# emonPi2C_V1_2.net
KiCad netlist of a schematic drawn in EAGLE
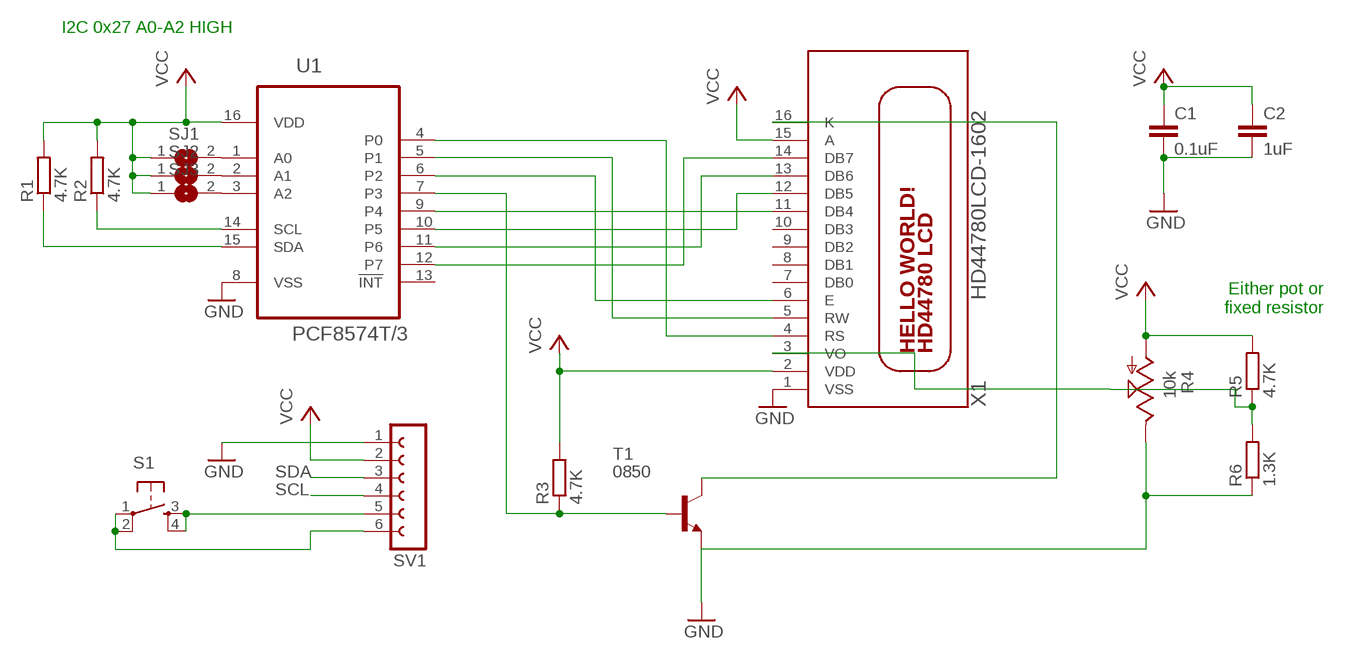
[diagram p0: schematic, sheet 1]

(export (version "E")
  (design (tool "Eeschema 10.0.6"))
  (components
    (comp (ref "C1")
      (value "0.1uF")
      (footprint "eagle-import:C0603")
      (libsource (lib "eagle-import") (part "C-EUC0603"))
    )
    (comp (ref "C2")
      (value "1uF")
      (footprint "eagle-import:C0603")
      (libsource (lib "eagle-import") (part "C-EUC0603"))
    )
    (comp (ref "R1")
      (value "4.7K")
      (footprint "eagle-import:R0603")
      (libsource (lib "eagle-import") (part "R-EU_R0603"))
    )
    (comp (ref "R2")
      (value "4.7K")
      (footprint "eagle-import:R0603")
      (libsource (lib "eagle-import") (part "R-EU_R0603"))
    )
    (comp (ref "R3")
      (value "4.7K")
      (footprint "eagle-import:R0603")
      (libsource (lib "eagle-import") (part "R-EU_R0603"))
    )
    (comp (ref "R4")
      (value "10k")
      (footprint "eagle-import:B25P")
      (libsource (lib "eagle-import") (part "TRIM_US-B25P"))
    )
    (comp (ref "R5")
      (value "4.7K")
      (footprint "eagle-import:R0603")
      (libsource (lib "eagle-import") (part "R-EU_R0603"))
    )
    (comp (ref "R6")
      (value "1.3K")
      (footprint "eagle-import:R0603")
      (libsource (lib "eagle-import") (part "R-EU_R0603"))
    )
    (comp (ref "S1")
      (value "TAC_SWITCHPTH")
      (footprint "eagle-import:TACTILE-PTH")
      (libsource (lib "eagle-import") (part "TAC_SWITCHPTH"))
    )
    (comp (ref "SJ1")
      (value "SOLDERJUMPERCLOSED")
      (footprint "eagle-import:SOLDERJUMPER_CLOSEDWIRE")
      (libsource (lib "eagle-import") (part "SOLDERJUMPERCLOSED"))
    )
    (comp (ref "SJ2")
      (value "SOLDERJUMPERCLOSED")
      (footprint "eagle-import:SOLDERJUMPER_CLOSEDWIRE")
      (libsource (lib "eagle-import") (part "SOLDERJUMPERCLOSED"))
    )
    (comp (ref "SJ3")
      (value "SOLDERJUMPERCLOSED")
      (footprint "eagle-import:SOLDERJUMPER_CLOSEDWIRE")
      (libsource (lib "eagle-import") (part "SOLDERJUMPERCLOSED"))
    )
    (comp (ref "SV1")
      (value "FE06-1")
      (footprint "eagle-import:FE06")
      (libsource (lib "eagle-import") (part "FE06-1"))
    )
    (comp (ref "T1")
      (value "0850")
      (footprint "eagle-import:SOT23")
      (libsource (lib "eagle-import") (part "BCX70SMD"))
    )
    (comp (ref "U1")
      (value "PCF8574T/3")
      (footprint "eagle-import:SOIC127P1032X265-16N")
      (libsource (lib "eagle-import") (part "PCF8574T/3"))
    )
    (comp (ref "X1")
      (value "HD44780LCD-1602")
      (footprint "eagle-import:LCD1602")
      (libsource (lib "eagle-import") (part "HD44780LCD-1602"))
    )
  )
  (nets
    (net (code "1") (name "/SCL") (class "Default")
      (node (ref "R2") (pin "1") (pinfunction "1_1") (pintype "passive"))
      (node (ref "SV1") (pin "4") (pinfunction "4_4") (pintype "passive"))
      (node (ref "U1") (pin "14") (pinfunction "SCL_14") (pintype "passive"))
    )
    (net (code "2") (name "/SDA") (class "Default")
      (node (ref "R1") (pin "1") (pinfunction "1_1") (pintype "passive"))
      (node (ref "SV1") (pin "3") (pinfunction "3_3") (pintype "passive"))
      (node (ref "U1") (pin "15") (pinfunction "SDA_15") (pintype "passive"))
    )
    (net (code "3") (name "GND") (class "Default")
      (node (ref "C1") (pin "2") (pinfunction "2_2") (pintype "passive"))
      (node (ref "C2") (pin "2") (pinfunction "2_2") (pintype "passive"))
      (node (ref "R4") (pin "E") (pinfunction "E_E") (pintype "passive"))
      (node (ref "R6") (pin "1") (pinfunction "1_1") (pintype "passive"))
      (node (ref "SV1") (pin "1") (pinfunction "1_1") (pintype "passive"))
      (node (ref "T1") (pin "2") (pinfunction "E_2") (pintype "passive"))
      (node (ref "U1") (pin "8") (pinfunction "VSS_8") (pintype "power_in"))
      (node (ref "X1") (pin "1") (pinfunction "VSS_1") (pintype "power_in"))
    )
    (net (code "4") (name "Net-(S1-Pad1)") (class "Default")
      (node (ref "S1") (pin "1") (pinfunction "1_1") (pintype "passive"))
      (node (ref "S1") (pin "2") (pinfunction "2_2") (pintype "passive"))
      (node (ref "SV1") (pin "6") (pinfunction "6_6") (pintype "passive"))
    )
    (net (code "5") (name "Net-(S1-Pad3)") (class "Default")
      (node (ref "S1") (pin "3") (pinfunction "3_3") (pintype "passive"))
      (node (ref "S1") (pin "4") (pinfunction "4_4") (pintype "passive"))
      (node (ref "SV1") (pin "5") (pinfunction "5_5") (pintype "passive"))
    )
    (net (code "6") (name "Net-(T1-B)") (class "Default")
      (node (ref "R3") (pin "1") (pinfunction "1_1") (pintype "passive"))
      (node (ref "T1") (pin "1") (pinfunction "B_1") (pintype "passive"))
      (node (ref "U1") (pin "7") (pinfunction "P3_7") (pintype "bidirectional"))
    )
    (net (code "7") (name "Net-(T1-C)") (class "Default")
      (node (ref "T1") (pin "3") (pinfunction "C_3") (pintype "passive"))
      (node (ref "X1") (pin "16") (pinfunction "K_16") (pintype "input"))
    )
    (net (code "8") (name "Net-(U1-A0)") (class "Default")
      (node (ref "SJ1") (pin "2") (pinfunction "2_2") (pintype "passive"))
      (node (ref "U1") (pin "1") (pinfunction "A0_1") (pintype "input"))
    )
    (net (code "9") (name "Net-(U1-A1)") (class "Default")
      (node (ref "SJ2") (pin "2") (pinfunction "2_2") (pintype "passive"))
      (node (ref "U1") (pin "2") (pinfunction "A1_2") (pintype "input"))
    )
    (net (code "10") (name "Net-(U1-A2)") (class "Default")
      (node (ref "SJ3") (pin "2") (pinfunction "2_2") (pintype "passive"))
      (node (ref "U1") (pin "3") (pinfunction "A2_3") (pintype "input"))
    )
    (net (code "11") (name "Net-(U1-P0)") (class "Default")
      (node (ref "U1") (pin "4") (pinfunction "P0_4") (pintype "bidirectional"))
      (node (ref "X1") (pin "4") (pinfunction "RS_4") (pintype "input"))
    )
    (net (code "12") (name "Net-(U1-P1)") (class "Default")
      (node (ref "U1") (pin "5") (pinfunction "P1_5") (pintype "bidirectional"))
      (node (ref "X1") (pin "5") (pinfunction "RW_5") (pintype "input"))
    )
    (net (code "13") (name "Net-(U1-P2)") (class "Default")
      (node (ref "U1") (pin "6") (pinfunction "P2_6") (pintype "bidirectional"))
      (node (ref "X1") (pin "6") (pinfunction "E_6") (pintype "input"))
    )
    (net (code "14") (name "Net-(U1-P4)") (class "Default")
      (node (ref "U1") (pin "9") (pinfunction "P4_9") (pintype "bidirectional"))
      (node (ref "X1") (pin "11") (pinfunction "DB4_11") (pintype "bidirectional"))
    )
    (net (code "15") (name "Net-(U1-P5)") (class "Default")
      (node (ref "U1") (pin "10") (pinfunction "P5_10") (pintype "bidirectional"))
      (node (ref "X1") (pin "12") (pinfunction "DB5_12") (pintype "bidirectional"))
    )
    (net (code "16") (name "Net-(U1-P6)") (class "Default")
      (node (ref "U1") (pin "11") (pinfunction "P6_11") (pintype "bidirectional"))
      (node (ref "X1") (pin "13") (pinfunction "DB6_13") (pintype "bidirectional"))
    )
    (net (code "17") (name "Net-(U1-P7)") (class "Default")
      (node (ref "U1") (pin "12") (pinfunction "P7_12") (pintype "bidirectional"))
      (node (ref "X1") (pin "14") (pinfunction "DB7_14") (pintype "bidirectional"))
    )
    (net (code "18") (name "Net-(X1-VO)") (class "Default")
      (node (ref "R4") (pin "S") (pinfunction "S_S") (pintype "passive"))
      (node (ref "R5") (pin "1") (pinfunction "1_1") (pintype "passive"))
      (node (ref "R6") (pin "2") (pinfunction "2_2") (pintype "passive"))
      (node (ref "X1") (pin "3") (pinfunction "VO_3") (pintype "input"))
    )
    (net (code "19") (name "VCC") (class "Default")
      (node (ref "C1") (pin "1") (pinfunction "1_1") (pintype "passive"))
      (node (ref "C2") (pin "1") (pinfunction "1_1") (pintype "passive"))
      (node (ref "R1") (pin "2") (pinfunction "2_2") (pintype "passive"))
      (node (ref "R2") (pin "2") (pinfunction "2_2") (pintype "passive"))
      (node (ref "R3") (pin "2") (pinfunction "2_2") (pintype "passive"))
      (node (ref "R4") (pin "A") (pinfunction "A_A") (pintype "passive"))
      (node (ref "R5") (pin "2") (pinfunction "2_2") (pintype "passive"))
      (node (ref "SJ1") (pin "1") (pinfunction "1_1") (pintype "passive"))
      (node (ref "SJ2") (pin "1") (pinfunction "1_1") (pintype "passive"))
      (node (ref "SJ3") (pin "1") (pinfunction "1_1") (pintype "passive"))
      (node (ref "SV1") (pin "2") (pinfunction "2_2") (pintype "passive"))
      (node (ref "U1") (pin "16") (pinfunction "VDD_16") (pintype "power_in"))
      (node (ref "X1") (pin "15") (pinfunction "A_15") (pintype "input"))
      (node (ref "X1") (pin "2") (pinfunction "VDD_2") (pintype "power_in"))
    )
    (net (code "20") (name "unconnected-(U1-~{INT}-Pad13)") (class "Default")
      (node (ref "U1") (pin "13") (pinfunction "~{INT}_13") (pintype "output"))
    )
    (net (code "21") (name "unconnected-(X1-DB0-Pad7)") (class "Default")
      (node (ref "X1") (pin "7") (pinfunction "DB0_7") (pintype "bidirectional"))
    )
    (net (code "22") (name "unconnected-(X1-DB1-Pad8)") (class "Default")
      (node (ref "X1") (pin "8") (pinfunction "DB1_8") (pintype "bidirectional"))
    )
    (net (code "23") (name "unconnected-(X1-DB2-Pad9)") (class "Default")
      (node (ref "X1") (pin "9") (pinfunction "DB2_9") (pintype "bidirectional"))
    )
    (net (code "24") (name "unconnected-(X1-DB3-Pad10)") (class "Default")
      (node (ref "X1") (pin "10") (pinfunction "DB3_10") (pintype "bidirectional"))
    )
  )
)
